# CO2_Sensor.net
KiCad netlist of a schematic drawn in Altium Designer
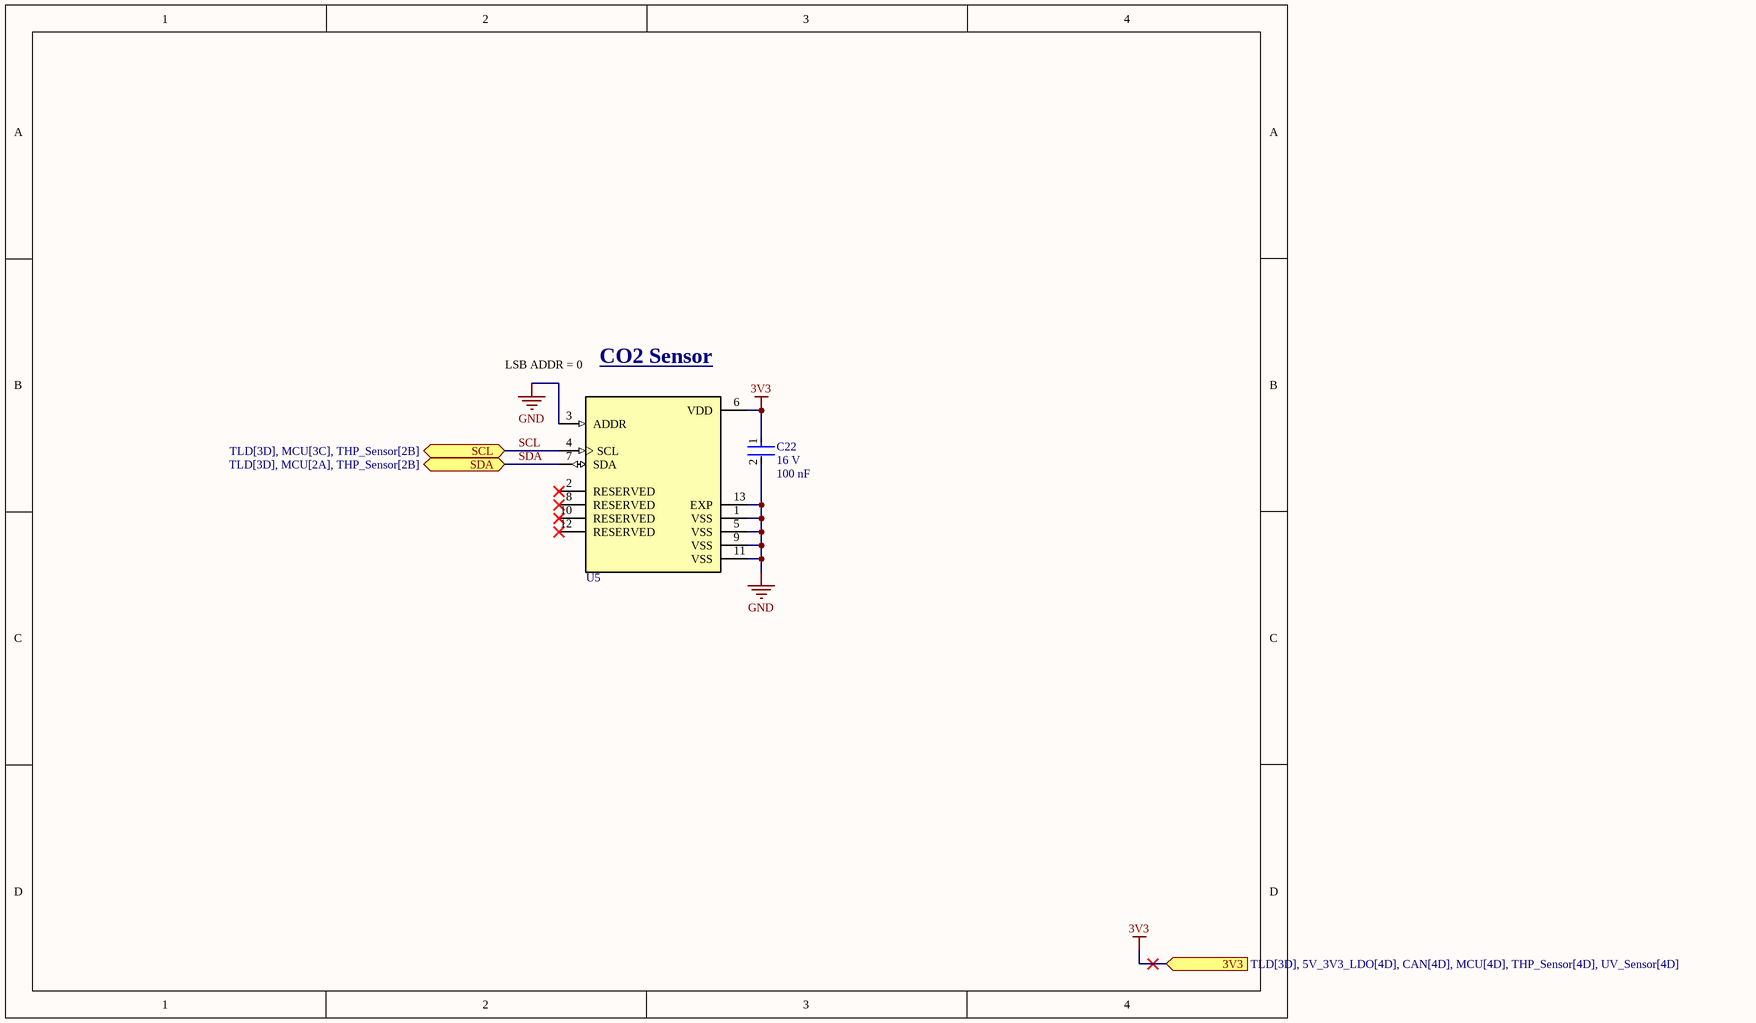
[diagram p0: CO2_Sensor.SchDoc]

(export (version "E")
  (design (tool "Eeschema 10.0.6"))
  (components
    (comp (ref "C22")
      (value "CC0402KRX7R7BB104")
      (footprint "CAP-0402")
      (description "CAP CER 0.1UF 16V X7R 0402")
      (fields (field (name "VOLTAGE RATING") "16 V") (field (name "CAPACITANCE") "100 nF"))
      (libsource (lib "JLC_25") (part "CAP-0.1U-0001"))
    )
    (comp (ref "U5")
      (value "STC31-C-R3")
      (footprint "XDCR_STC31-C-R3")
      (description "SENSOR CARBON DIOXIDE I2C OUTPUT")
      (fields (field (name "MF") "Sensirion"))
      (libsource (lib "MasterLib") (part "SENS-CO2"))
    )
  )
  (nets
    (net (code "1") (name "/SCL") (class "Default")
      (node (ref "U5") (pin "4") (pinfunction "SCL_4") (pintype "input"))
    )
    (net (code "2") (name "/SDA") (class "Default")
      (node (ref "U5") (pin "7") (pinfunction "SDA_7") (pintype "bidirectional"))
    )
    (net (code "3") (name "3V3") (class "Default")
      (node (ref "C22") (pin "1") (pinfunction "1_1") (pintype "passive"))
      (node (ref "U5") (pin "6") (pinfunction "VDD_6") (pintype "power_in"))
    )
    (net (code "4") (name "GND") (class "Default")
      (node (ref "C22") (pin "2") (pinfunction "2_2") (pintype "passive"))
      (node (ref "U5") (pin "1") (pinfunction "VSS_1") (pintype "power_in"))
      (node (ref "U5") (pin "11") (pinfunction "VSS_11") (pintype "power_in"))
      (node (ref "U5") (pin "13") (pinfunction "EXP_13") (pintype "power_in"))
      (node (ref "U5") (pin "3") (pinfunction "ADDR_3") (pintype "input"))
      (node (ref "U5") (pin "5") (pinfunction "VSS_5") (pintype "power_in"))
      (node (ref "U5") (pin "9") (pinfunction "VSS_9") (pintype "power_in"))
    )
    (net (code "5") (name "unconnected-(U5-RESERVED-Pad2)") (class "Default")
      (node (ref "U5") (pin "2") (pinfunction "RESERVED_2") (pintype "passive+no_connect"))
    )
    (net (code "6") (name "unconnected-(U5-RESERVED-Pad8)") (class "Default")
      (node (ref "U5") (pin "8") (pinfunction "RESERVED_8") (pintype "passive+no_connect"))
    )
    (net (code "7") (name "unconnected-(U5-RESERVED-Pad10)") (class "Default")
      (node (ref "U5") (pin "10") (pinfunction "RESERVED_10") (pintype "passive+no_connect"))
    )
    (net (code "8") (name "unconnected-(U5-RESERVED-Pad12)") (class "Default")
      (node (ref "U5") (pin "12") (pinfunction "RESERVED_12") (pintype "passive+no_connect"))
    )
  )
)
